# stim_headstage_32.net
KiCad netlist of a schematic drawn in EAGLE
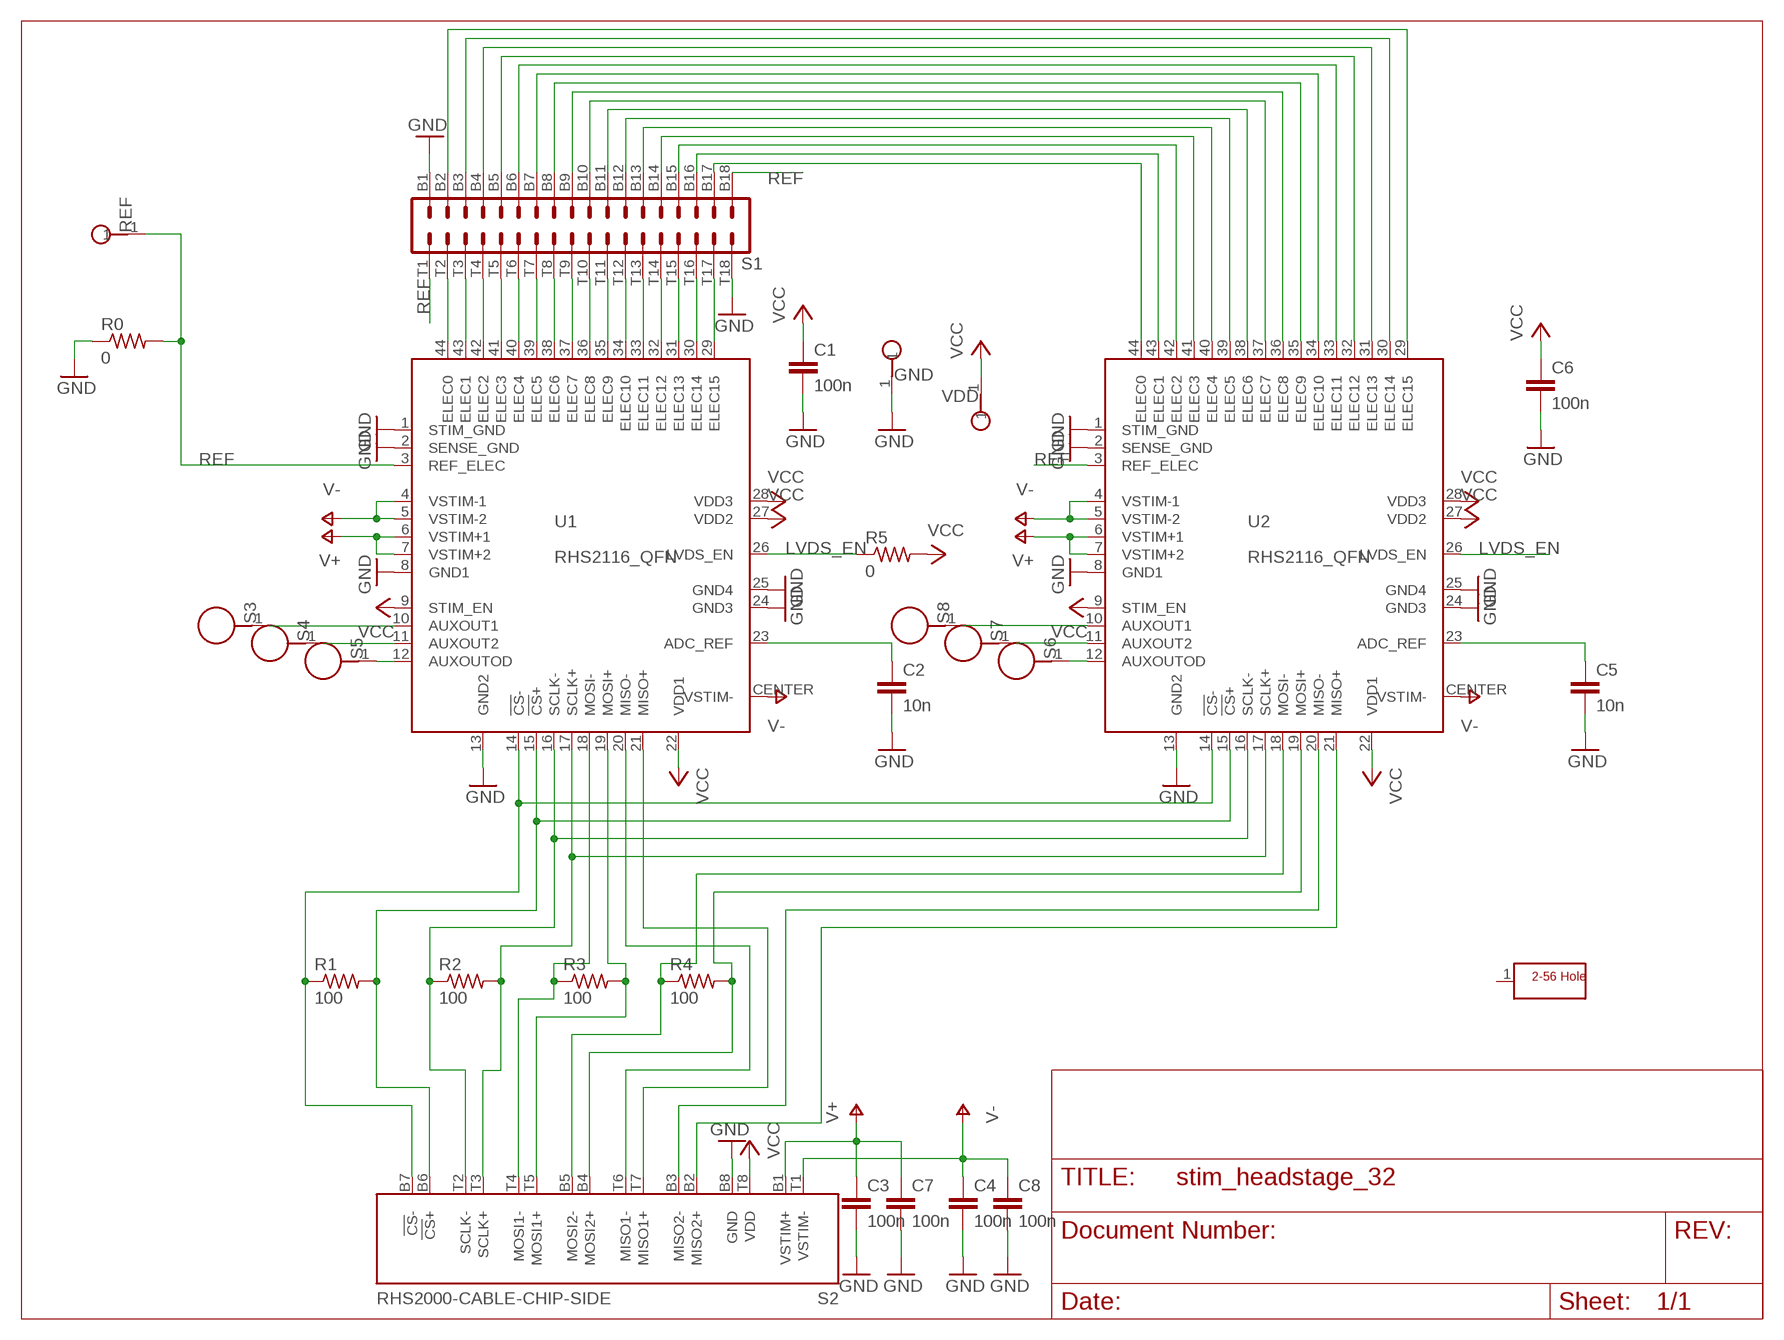
[diagram p0: schematic, sheet 1]

(export (version "E")
  (design (tool "Eeschema 10.0.6"))
  (components
    (comp (ref "C1")
      (value "100n")
      (footprint "eagle-import:0402")
      (libsource (lib "eagle-import") (part "C_0402"))
    )
    (comp (ref "C2")
      (value "10n")
      (footprint "eagle-import:0402")
      (libsource (lib "eagle-import") (part "C_0402"))
    )
    (comp (ref "C3")
      (value "100n")
      (footprint "eagle-import:0402")
      (libsource (lib "eagle-import") (part "C_0402"))
    )
    (comp (ref "C4")
      (value "100n")
      (footprint "eagle-import:0402")
      (libsource (lib "eagle-import") (part "C_0402"))
    )
    (comp (ref "C5")
      (value "10n")
      (footprint "eagle-import:0402")
      (libsource (lib "eagle-import") (part "C_0402"))
    )
    (comp (ref "C6")
      (value "100n")
      (footprint "eagle-import:0402")
      (libsource (lib "eagle-import") (part "C_0402"))
    )
    (comp (ref "C7")
      (value "100n")
      (footprint "eagle-import:0402")
      (libsource (lib "eagle-import") (part "C_0402"))
    )
    (comp (ref "C8")
      (value "100n")
      (footprint "eagle-import:0402")
      (libsource (lib "eagle-import") (part "C_0402"))
    )
    (comp (ref "GND")
      (value "TESTPOINT_SMALL")
      (footprint "eagle-import:TESTPOINT_SMALL")
      (libsource (lib "eagle-import") (part "TESTPOINT_SMALL"))
    )
    (comp (ref "H1")
      (value "SCREW_HOLE_2-56")
      (footprint "eagle-import:SCREW_HOLE_2-56")
      (libsource (lib "eagle-import") (part "SCREW_HOLE_2-56"))
    )
    (comp (ref "R0")
      (value "0")
      (footprint "eagle-import:0402")
      (libsource (lib "eagle-import") (part "R_0402"))
    )
    (comp (ref "R1")
      (value "100")
      (footprint "eagle-import:0201")
      (libsource (lib "eagle-import") (part "R_0201"))
    )
    (comp (ref "R2")
      (value "100")
      (footprint "eagle-import:0201")
      (libsource (lib "eagle-import") (part "R_0201"))
    )
    (comp (ref "R3")
      (value "100")
      (footprint "eagle-import:0201")
      (libsource (lib "eagle-import") (part "R_0201"))
    )
    (comp (ref "R4")
      (value "100")
      (footprint "eagle-import:0201")
      (libsource (lib "eagle-import") (part "R_0201"))
    )
    (comp (ref "R5")
      (value "0")
      (footprint "eagle-import:0201")
      (libsource (lib "eagle-import") (part "R_0201"))
    )
    (comp (ref "REF")
      (value "TESTPOINT_SMALL")
      (footprint "eagle-import:TESTPOINT_SMALL")
      (libsource (lib "eagle-import") (part "TESTPOINT_SMALL"))
    )
    (comp (ref "S1")
      (value "OMNETICS_A79025")
      (footprint "eagle-import:OMNETICS_A79025")
      (libsource (lib "eagle-import") (part "OMNETICS_A79025"))
    )
    (comp (ref "S2")
      (value "RHS2000-CABLE-CHIP-SIDE")
      (footprint "eagle-import:OMNETICS_PZN-16-AA")
      (libsource (lib "eagle-import") (part "RHS2000-CABLE-CHIP-SIDE"))
    )
    (comp (ref "S3")
      (value "SMD_CONTACT_1_0_X_1_2")
      (footprint "eagle-import:SMD_PAD_1_0_X_1_2")
      (libsource (lib "eagle-import") (part "SMD_CONTACT_1_0_X_1_2"))
    )
    (comp (ref "S4")
      (value "SMD_CONTACT_1_0_X_1_2")
      (footprint "eagle-import:SMD_PAD_1_0_X_1_2")
      (libsource (lib "eagle-import") (part "SMD_CONTACT_1_0_X_1_2"))
    )
    (comp (ref "S5")
      (value "SMD_CONTACT_1_0_X_1_2")
      (footprint "eagle-import:SMD_PAD_1_0_X_1_2")
      (libsource (lib "eagle-import") (part "SMD_CONTACT_1_0_X_1_2"))
    )
    (comp (ref "S6")
      (value "SMD_CONTACT_1_0_X_1_2")
      (footprint "eagle-import:SMD_PAD_1_0_X_1_2")
      (libsource (lib "eagle-import") (part "SMD_CONTACT_1_0_X_1_2"))
    )
    (comp (ref "S7")
      (value "SMD_CONTACT_1_0_X_1_2")
      (footprint "eagle-import:SMD_PAD_1_0_X_1_2")
      (libsource (lib "eagle-import") (part "SMD_CONTACT_1_0_X_1_2"))
    )
    (comp (ref "S8")
      (value "SMD_CONTACT_1_0_X_1_2")
      (footprint "eagle-import:SMD_PAD_1_0_X_1_2")
      (libsource (lib "eagle-import") (part "SMD_CONTACT_1_0_X_1_2"))
    )
    (comp (ref "U1")
      (value "RHS2116_QFN")
      (footprint "eagle-import:QFN44_7_X_7")
      (libsource (lib "eagle-import") (part "RHS2116_QFN"))
    )
    (comp (ref "U2")
      (value "RHS2116_QFN")
      (footprint "eagle-import:QFN44_7_X_7")
      (libsource (lib "eagle-import") (part "RHS2116_QFN"))
    )
    (comp (ref "VDD")
      (value "TESTPOINT_SMALL")
      (footprint "eagle-import:TESTPOINT_SMALL")
      (libsource (lib "eagle-import") (part "TESTPOINT_SMALL"))
    )
  )
  (nets
    (net (code "1") (name "/LVDS_EN") (class "Default")
      (node (ref "R5") (pin "1") (pinfunction "1_1") (pintype "passive"))
      (node (ref "U1") (pin "26") (pinfunction "LVDS_EN_26") (pintype "input"))
      (node (ref "U2") (pin "26") (pinfunction "LVDS_EN_26") (pintype "input"))
    )
    (net (code "2") (name "/REF") (class "Default")
      (node (ref "R0") (pin "2") (pinfunction "2_2") (pintype "passive"))
      (node (ref "REF") (pin "1") (pinfunction "1_1") (pintype "passive"))
      (node (ref "S1") (pin "B18") (pinfunction "B18_B18") (pintype "passive"))
      (node (ref "S1") (pin "T1") (pinfunction "T1_T1") (pintype "passive"))
      (node (ref "U1") (pin "3") (pinfunction "REF_ELEC_3") (pintype "input"))
      (node (ref "U2") (pin "3") (pinfunction "REF_ELEC_3") (pintype "input"))
    )
    (net (code "3") (name "GND") (class "Default")
      (node (ref "C1") (pin "2") (pinfunction "2_2") (pintype "passive"))
      (node (ref "C2") (pin "2") (pinfunction "2_2") (pintype "passive"))
      (node (ref "C3") (pin "2") (pinfunction "2_2") (pintype "passive"))
      (node (ref "C4") (pin "2") (pinfunction "2_2") (pintype "passive"))
      (node (ref "C5") (pin "2") (pinfunction "2_2") (pintype "passive"))
      (node (ref "C6") (pin "2") (pinfunction "2_2") (pintype "passive"))
      (node (ref "C7") (pin "2") (pinfunction "2_2") (pintype "passive"))
      (node (ref "C8") (pin "2") (pinfunction "2_2") (pintype "passive"))
      (node (ref "GND") (pin "1") (pinfunction "1_1") (pintype "passive"))
      (node (ref "R0") (pin "1") (pinfunction "1_1") (pintype "passive"))
      (node (ref "S1") (pin "B1") (pinfunction "B1_B1") (pintype "passive"))
      (node (ref "S1") (pin "T18") (pinfunction "T18_T18") (pintype "passive"))
      (node (ref "S2") (pin "B8") (pinfunction "GND_B8") (pintype "power_in"))
      (node (ref "U1") (pin "1") (pinfunction "STIM_GND_1") (pintype "power_in"))
      (node (ref "U1") (pin "13") (pinfunction "GND2_13") (pintype "power_in"))
      (node (ref "U1") (pin "2") (pinfunction "SENSE_GND_2") (pintype "power_in"))
      (node (ref "U1") (pin "24") (pinfunction "GND3_24") (pintype "power_in"))
      (node (ref "U1") (pin "25") (pinfunction "GND4_25") (pintype "power_in"))
      (node (ref "U1") (pin "8") (pinfunction "GND1_8") (pintype "power_in"))
      (node (ref "U2") (pin "1") (pinfunction "STIM_GND_1") (pintype "power_in"))
      (node (ref "U2") (pin "13") (pinfunction "GND2_13") (pintype "power_in"))
      (node (ref "U2") (pin "2") (pinfunction "SENSE_GND_2") (pintype "power_in"))
      (node (ref "U2") (pin "24") (pinfunction "GND3_24") (pintype "power_in"))
      (node (ref "U2") (pin "25") (pinfunction "GND4_25") (pintype "power_in"))
      (node (ref "U2") (pin "8") (pinfunction "GND1_8") (pintype "power_in"))
    )
    (net (code "4") (name "Net-(S2-MISO1+)") (class "Default")
      (node (ref "S2") (pin "T7") (pinfunction "MISO1+_T7") (pintype "bidirectional"))
      (node (ref "U1") (pin "21") (pinfunction "MISO+_21") (pintype "output"))
    )
    (net (code "5") (name "Net-(S2-MISO1-)") (class "Default")
      (node (ref "S2") (pin "T6") (pinfunction "MISO1-_T6") (pintype "bidirectional"))
      (node (ref "U1") (pin "20") (pinfunction "MISO-_20") (pintype "output"))
    )
    (net (code "6") (name "Net-(S2-MISO2+)") (class "Default")
      (node (ref "S2") (pin "B2") (pinfunction "MISO2+_B2") (pintype "bidirectional"))
      (node (ref "U2") (pin "21") (pinfunction "MISO+_21") (pintype "output"))
    )
    (net (code "7") (name "Net-(S2-MISO2-)") (class "Default")
      (node (ref "S2") (pin "B3") (pinfunction "MISO2-_B3") (pintype "bidirectional"))
      (node (ref "U2") (pin "20") (pinfunction "MISO-_20") (pintype "output"))
    )
    (net (code "8") (name "Net-(S2-MOSI1+)") (class "Default")
      (node (ref "R3") (pin "2") (pinfunction "2_2") (pintype "passive"))
      (node (ref "S2") (pin "T5") (pinfunction "MOSI1+_T5") (pintype "bidirectional"))
      (node (ref "U1") (pin "19") (pinfunction "MOSI+_19") (pintype "input"))
    )
    (net (code "9") (name "Net-(S2-MOSI1-)") (class "Default")
      (node (ref "R3") (pin "1") (pinfunction "1_1") (pintype "passive"))
      (node (ref "S2") (pin "T4") (pinfunction "MOSI1-_T4") (pintype "bidirectional"))
      (node (ref "U1") (pin "18") (pinfunction "MOSI-_18") (pintype "input"))
    )
    (net (code "10") (name "Net-(S2-MOSI2+)") (class "Default")
      (node (ref "R4") (pin "2") (pinfunction "2_2") (pintype "passive"))
      (node (ref "S2") (pin "B4") (pinfunction "MOSI2+_B4") (pintype "bidirectional"))
      (node (ref "U2") (pin "19") (pinfunction "MOSI+_19") (pintype "input"))
    )
    (net (code "11") (name "Net-(S2-MOSI2-)") (class "Default")
      (node (ref "R4") (pin "1") (pinfunction "1_1") (pintype "passive"))
      (node (ref "S2") (pin "B5") (pinfunction "MOSI2-_B5") (pintype "bidirectional"))
      (node (ref "U2") (pin "18") (pinfunction "MOSI-_18") (pintype "input"))
    )
    (net (code "12") (name "Net-(S2-SCLK+)") (class "Default")
      (node (ref "R2") (pin "2") (pinfunction "2_2") (pintype "passive"))
      (node (ref "S2") (pin "T3") (pinfunction "SCLK+_T3") (pintype "bidirectional"))
      (node (ref "U1") (pin "17") (pinfunction "SCLK+_17") (pintype "input"))
      (node (ref "U2") (pin "17") (pinfunction "SCLK+_17") (pintype "input"))
    )
    (net (code "13") (name "Net-(S2-SCLK-)") (class "Default")
      (node (ref "R2") (pin "1") (pinfunction "1_1") (pintype "passive"))
      (node (ref "S2") (pin "T2") (pinfunction "SCLK-_T2") (pintype "bidirectional"))
      (node (ref "U1") (pin "16") (pinfunction "SCLK-_16") (pintype "input"))
      (node (ref "U2") (pin "16") (pinfunction "SCLK-_16") (pintype "input"))
    )
    (net (code "14") (name "Net-(S2-~{CS}+)") (class "Default")
      (node (ref "R1") (pin "2") (pinfunction "2_2") (pintype "passive"))
      (node (ref "S2") (pin "B6") (pinfunction "~{CS}+_B6") (pintype "bidirectional"))
      (node (ref "U1") (pin "15") (pinfunction "~{CS}+_15") (pintype "input"))
      (node (ref "U2") (pin "15") (pinfunction "~{CS}+_15") (pintype "input"))
    )
    (net (code "15") (name "Net-(S2-~{CS}-)") (class "Default")
      (node (ref "R1") (pin "1") (pinfunction "1_1") (pintype "passive"))
      (node (ref "S2") (pin "B7") (pinfunction "~{CS}-_B7") (pintype "bidirectional"))
      (node (ref "U1") (pin "14") (pinfunction "~{CS}-_14") (pintype "input"))
      (node (ref "U2") (pin "14") (pinfunction "~{CS}-_14") (pintype "input"))
    )
    (net (code "16") (name "Net-(U1-ADC_REF)") (class "Default")
      (node (ref "C2") (pin "1") (pinfunction "1_1") (pintype "passive"))
      (node (ref "U1") (pin "23") (pinfunction "ADC_REF_23") (pintype "passive"))
    )
    (net (code "17") (name "Net-(U1-AUXOUT1)") (class "Default")
      (node (ref "S3") (pin "1") (pinfunction "1_1") (pintype "passive"))
      (node (ref "U1") (pin "10") (pinfunction "AUXOUT1_10") (pintype "tri_state"))
    )
    (net (code "18") (name "Net-(U1-AUXOUT2)") (class "Default")
      (node (ref "S4") (pin "1") (pinfunction "1_1") (pintype "passive"))
      (node (ref "U1") (pin "11") (pinfunction "AUXOUT2_11") (pintype "tri_state"))
    )
    (net (code "19") (name "Net-(U1-AUXOUTOD)") (class "Default")
      (node (ref "S5") (pin "1") (pinfunction "1_1") (pintype "passive"))
      (node (ref "U1") (pin "12") (pinfunction "AUXOUTOD_12") (pintype "open_collector"))
    )
    (net (code "20") (name "Net-(U1-ELEC0)") (class "Default")
      (node (ref "S1") (pin "T2") (pinfunction "T2_T2") (pintype "passive"))
      (node (ref "U1") (pin "44") (pinfunction "ELEC0_44") (pintype "bidirectional"))
    )
    (net (code "21") (name "Net-(U1-ELEC1)") (class "Default")
      (node (ref "S1") (pin "T3") (pinfunction "T3_T3") (pintype "passive"))
      (node (ref "U1") (pin "43") (pinfunction "ELEC1_43") (pintype "bidirectional"))
    )
    (net (code "22") (name "Net-(U1-ELEC2)") (class "Default")
      (node (ref "S1") (pin "T4") (pinfunction "T4_T4") (pintype "passive"))
      (node (ref "U1") (pin "42") (pinfunction "ELEC2_42") (pintype "bidirectional"))
    )
    (net (code "23") (name "Net-(U1-ELEC3)") (class "Default")
      (node (ref "S1") (pin "T5") (pinfunction "T5_T5") (pintype "passive"))
      (node (ref "U1") (pin "41") (pinfunction "ELEC3_41") (pintype "bidirectional"))
    )
    (net (code "24") (name "Net-(U1-ELEC4)") (class "Default")
      (node (ref "S1") (pin "T6") (pinfunction "T6_T6") (pintype "passive"))
      (node (ref "U1") (pin "40") (pinfunction "ELEC4_40") (pintype "bidirectional"))
    )
    (net (code "25") (name "Net-(U1-ELEC5)") (class "Default")
      (node (ref "S1") (pin "T7") (pinfunction "T7_T7") (pintype "passive"))
      (node (ref "U1") (pin "39") (pinfunction "ELEC5_39") (pintype "bidirectional"))
    )
    (net (code "26") (name "Net-(U1-ELEC6)") (class "Default")
      (node (ref "S1") (pin "T8") (pinfunction "T8_T8") (pintype "passive"))
      (node (ref "U1") (pin "38") (pinfunction "ELEC6_38") (pintype "bidirectional"))
    )
    (net (code "27") (name "Net-(U1-ELEC7)") (class "Default")
      (node (ref "S1") (pin "T9") (pinfunction "T9_T9") (pintype "passive"))
      (node (ref "U1") (pin "37") (pinfunction "ELEC7_37") (pintype "bidirectional"))
    )
    (net (code "28") (name "Net-(U1-ELEC8)") (class "Default")
      (node (ref "S1") (pin "T10") (pinfunction "T10_T10") (pintype "passive"))
      (node (ref "U1") (pin "36") (pinfunction "ELEC8_36") (pintype "bidirectional"))
    )
    (net (code "29") (name "Net-(U1-ELEC9)") (class "Default")
      (node (ref "S1") (pin "T11") (pinfunction "T11_T11") (pintype "passive"))
      (node (ref "U1") (pin "35") (pinfunction "ELEC9_35") (pintype "bidirectional"))
    )
    (net (code "30") (name "Net-(U1-ELEC10)") (class "Default")
      (node (ref "S1") (pin "T12") (pinfunction "T12_T12") (pintype "passive"))
      (node (ref "U1") (pin "34") (pinfunction "ELEC10_34") (pintype "bidirectional"))
    )
    (net (code "31") (name "Net-(U1-ELEC11)") (class "Default")
      (node (ref "S1") (pin "T13") (pinfunction "T13_T13") (pintype "passive"))
      (node (ref "U1") (pin "33") (pinfunction "ELEC11_33") (pintype "bidirectional"))
    )
    (net (code "32") (name "Net-(U1-ELEC12)") (class "Default")
      (node (ref "S1") (pin "T14") (pinfunction "T14_T14") (pintype "passive"))
      (node (ref "U1") (pin "32") (pinfunction "ELEC12_32") (pintype "bidirectional"))
    )
    (net (code "33") (name "Net-(U1-ELEC13)") (class "Default")
      (node (ref "S1") (pin "T15") (pinfunction "T15_T15") (pintype "passive"))
      (node (ref "U1") (pin "31") (pinfunction "ELEC13_31") (pintype "bidirectional"))
    )
    (net (code "34") (name "Net-(U1-ELEC14)") (class "Default")
      (node (ref "S1") (pin "T16") (pinfunction "T16_T16") (pintype "passive"))
      (node (ref "U1") (pin "30") (pinfunction "ELEC14_30") (pintype "bidirectional"))
    )
    (net (code "35") (name "Net-(U1-ELEC15)") (class "Default")
      (node (ref "S1") (pin "T17") (pinfunction "T17_T17") (pintype "passive"))
      (node (ref "U1") (pin "29") (pinfunction "ELEC15_29") (pintype "bidirectional"))
    )
    (net (code "36") (name "Net-(U2-ADC_REF)") (class "Default")
      (node (ref "C5") (pin "1") (pinfunction "1_1") (pintype "passive"))
      (node (ref "U2") (pin "23") (pinfunction "ADC_REF_23") (pintype "passive"))
    )
    (net (code "37") (name "Net-(U2-AUXOUT1)") (class "Default")
      (node (ref "S8") (pin "1") (pinfunction "1_1") (pintype "passive"))
      (node (ref "U2") (pin "10") (pinfunction "AUXOUT1_10") (pintype "tri_state"))
    )
    (net (code "38") (name "Net-(U2-AUXOUT2)") (class "Default")
      (node (ref "S7") (pin "1") (pinfunction "1_1") (pintype "passive"))
      (node (ref "U2") (pin "11") (pinfunction "AUXOUT2_11") (pintype "tri_state"))
    )
    (net (code "39") (name "Net-(U2-AUXOUTOD)") (class "Default")
      (node (ref "S6") (pin "1") (pinfunction "1_1") (pintype "passive"))
      (node (ref "U2") (pin "12") (pinfunction "AUXOUTOD_12") (pintype "open_collector"))
    )
    (net (code "40") (name "Net-(U2-ELEC0)") (class "Default")
      (node (ref "S1") (pin "B17") (pinfunction "B17_B17") (pintype "passive"))
      (node (ref "U2") (pin "44") (pinfunction "ELEC0_44") (pintype "bidirectional"))
    )
    (net (code "41") (name "Net-(U2-ELEC1)") (class "Default")
      (node (ref "S1") (pin "B16") (pinfunction "B16_B16") (pintype "passive"))
      (node (ref "U2") (pin "43") (pinfunction "ELEC1_43") (pintype "bidirectional"))
    )
    (net (code "42") (name "Net-(U2-ELEC2)") (class "Default")
      (node (ref "S1") (pin "B15") (pinfunction "B15_B15") (pintype "passive"))
      (node (ref "U2") (pin "42") (pinfunction "ELEC2_42") (pintype "bidirectional"))
    )
    (net (code "43") (name "Net-(U2-ELEC3)") (class "Default")
      (node (ref "S1") (pin "B14") (pinfunction "B14_B14") (pintype "passive"))
      (node (ref "U2") (pin "41") (pinfunction "ELEC3_41") (pintype "bidirectional"))
    )
    (net (code "44") (name "Net-(U2-ELEC4)") (class "Default")
      (node (ref "S1") (pin "B13") (pinfunction "B13_B13") (pintype "passive"))
      (node (ref "U2") (pin "40") (pinfunction "ELEC4_40") (pintype "bidirectional"))
    )
    (net (code "45") (name "Net-(U2-ELEC5)") (class "Default")
      (node (ref "S1") (pin "B12") (pinfunction "B12_B12") (pintype "passive"))
      (node (ref "U2") (pin "39") (pinfunction "ELEC5_39") (pintype "bidirectional"))
    )
    (net (code "46") (name "Net-(U2-ELEC6)") (class "Default")
      (node (ref "S1") (pin "B11") (pinfunction "B11_B11") (pintype "passive"))
      (node (ref "U2") (pin "38") (pinfunction "ELEC6_38") (pintype "bidirectional"))
    )
    (net (code "47") (name "Net-(U2-ELEC7)") (class "Default")
      (node (ref "S1") (pin "B10") (pinfunction "B10_B10") (pintype "passive"))
      (node (ref "U2") (pin "37") (pinfunction "ELEC7_37") (pintype "bidirectional"))
    )
    (net (code "48") (name "Net-(U2-ELEC8)") (class "Default")
      (node (ref "S1") (pin "B9") (pinfunction "B9_B9") (pintype "passive"))
      (node (ref "U2") (pin "36") (pinfunction "ELEC8_36") (pintype "bidirectional"))
    )
    (net (code "49") (name "Net-(U2-ELEC9)") (class "Default")
      (node (ref "S1") (pin "B8") (pinfunction "B8_B8") (pintype "passive"))
      (node (ref "U2") (pin "35") (pinfunction "ELEC9_35") (pintype "bidirectional"))
    )
    (net (code "50") (name "Net-(U2-ELEC10)") (class "Default")
      (node (ref "S1") (pin "B7") (pinfunction "B7_B7") (pintype "passive"))
      (node (ref "U2") (pin "34") (pinfunction "ELEC10_34") (pintype "bidirectional"))
    )
    (net (code "51") (name "Net-(U2-ELEC11)") (class "Default")
      (node (ref "S1") (pin "B6") (pinfunction "B6_B6") (pintype "passive"))
      (node (ref "U2") (pin "33") (pinfunction "ELEC11_33") (pintype "bidirectional"))
    )
    (net (code "52") (name "Net-(U2-ELEC12)") (class "Default")
      (node (ref "S1") (pin "B5") (pinfunction "B5_B5") (pintype "passive"))
      (node (ref "U2") (pin "32") (pinfunction "ELEC12_32") (pintype "bidirectional"))
    )
    (net (code "53") (name "Net-(U2-ELEC13)") (class "Default")
      (node (ref "S1") (pin "B4") (pinfunction "B4_B4") (pintype "passive"))
      (node (ref "U2") (pin "31") (pinfunction "ELEC13_31") (pintype "bidirectional"))
    )
    (net (code "54") (name "Net-(U2-ELEC14)") (class "Default")
      (node (ref "S1") (pin "B3") (pinfunction "B3_B3") (pintype "passive"))
      (node (ref "U2") (pin "30") (pinfunction "ELEC14_30") (pintype "bidirectional"))
    )
    (net (code "55") (name "Net-(U2-ELEC15)") (class "Default")
      (node (ref "S1") (pin "B2") (pinfunction "B2_B2") (pintype "passive"))
      (node (ref "U2") (pin "29") (pinfunction "ELEC15_29") (pintype "bidirectional"))
    )
    (net (code "56") (name "V+") (class "Default")
      (node (ref "C3") (pin "1") (pinfunction "1_1") (pintype "passive"))
      (node (ref "C7") (pin "1") (pinfunction "1_1") (pintype "passive"))
      (node (ref "S2") (pin "B1") (pinfunction "VSTIM+_B1") (pintype "power_in"))
      (node (ref "U1") (pin "6") (pinfunction "VSTIM+1_6") (pintype "power_in"))
      (node (ref "U1") (pin "7") (pinfunction "VSTIM+2_7") (pintype "power_in"))
      (node (ref "U2") (pin "6") (pinfunction "VSTIM+1_6") (pintype "power_in"))
      (node (ref "U2") (pin "7") (pinfunction "VSTIM+2_7") (pintype "power_in"))
    )
    (net (code "57") (name "V-") (class "Default")
      (node (ref "C4") (pin "1") (pinfunction "1_1") (pintype "passive"))
      (node (ref "C8") (pin "1") (pinfunction "1_1") (pintype "passive"))
      (node (ref "S2") (pin "T1") (pinfunction "VSTIM-_T1") (pintype "power_in"))
      (node (ref "U1") (pin "4") (pinfunction "VSTIM-1_4") (pintype "power_in"))
      (node (ref "U1") (pin "5") (pinfunction "VSTIM-2_5") (pintype "power_in"))
      (node (ref "U1") (pin "CENTER") (pinfunction "VSTIM-_CENTER") (pintype "power_in"))
      (node (ref "U2") (pin "4") (pinfunction "VSTIM-1_4") (pintype "power_in"))
      (node (ref "U2") (pin "5") (pinfunction "VSTIM-2_5") (pintype "power_in"))
      (node (ref "U2") (pin "CENTER") (pinfunction "VSTIM-_CENTER") (pintype "power_in"))
    )
    (net (code "58") (name "VCC") (class "Default")
      (node (ref "C1") (pin "1") (pinfunction "1_1") (pintype "passive"))
      (node (ref "C6") (pin "1") (pinfunction "1_1") (pintype "passive"))
      (node (ref "R5") (pin "2") (pinfunction "2_2") (pintype "passive"))
      (node (ref "S2") (pin "T8") (pinfunction "VDD_T8") (pintype "bidirectional"))
      (node (ref "U1") (pin "22") (pinfunction "VDD1_22") (pintype "power_in"))
      (node (ref "U1") (pin "27") (pinfunction "VDD2_27") (pintype "power_in"))
      (node (ref "U1") (pin "28") (pinfunction "VDD3_28") (pintype "power_in"))
      (node (ref "U1") (pin "9") (pinfunction "STIM_EN_9") (pintype "input"))
      (node (ref "U2") (pin "22") (pinfunction "VDD1_22") (pintype "power_in"))
      (node (ref "U2") (pin "27") (pinfunction "VDD2_27") (pintype "power_in"))
      (node (ref "U2") (pin "28") (pinfunction "VDD3_28") (pintype "power_in"))
      (node (ref "U2") (pin "9") (pinfunction "STIM_EN_9") (pintype "input"))
      (node (ref "VDD") (pin "1") (pinfunction "1_1") (pintype "passive"))
    )
    (net (code "59") (name "unconnected-(H1-Pad1)") (class "Default")
      (node (ref "H1") (pin "1") (pinfunction "1_1") (pintype "passive"))
    )
  )
)
